# audio_chip.net
KiCad netlist of a schematic drawn in EasyEDA
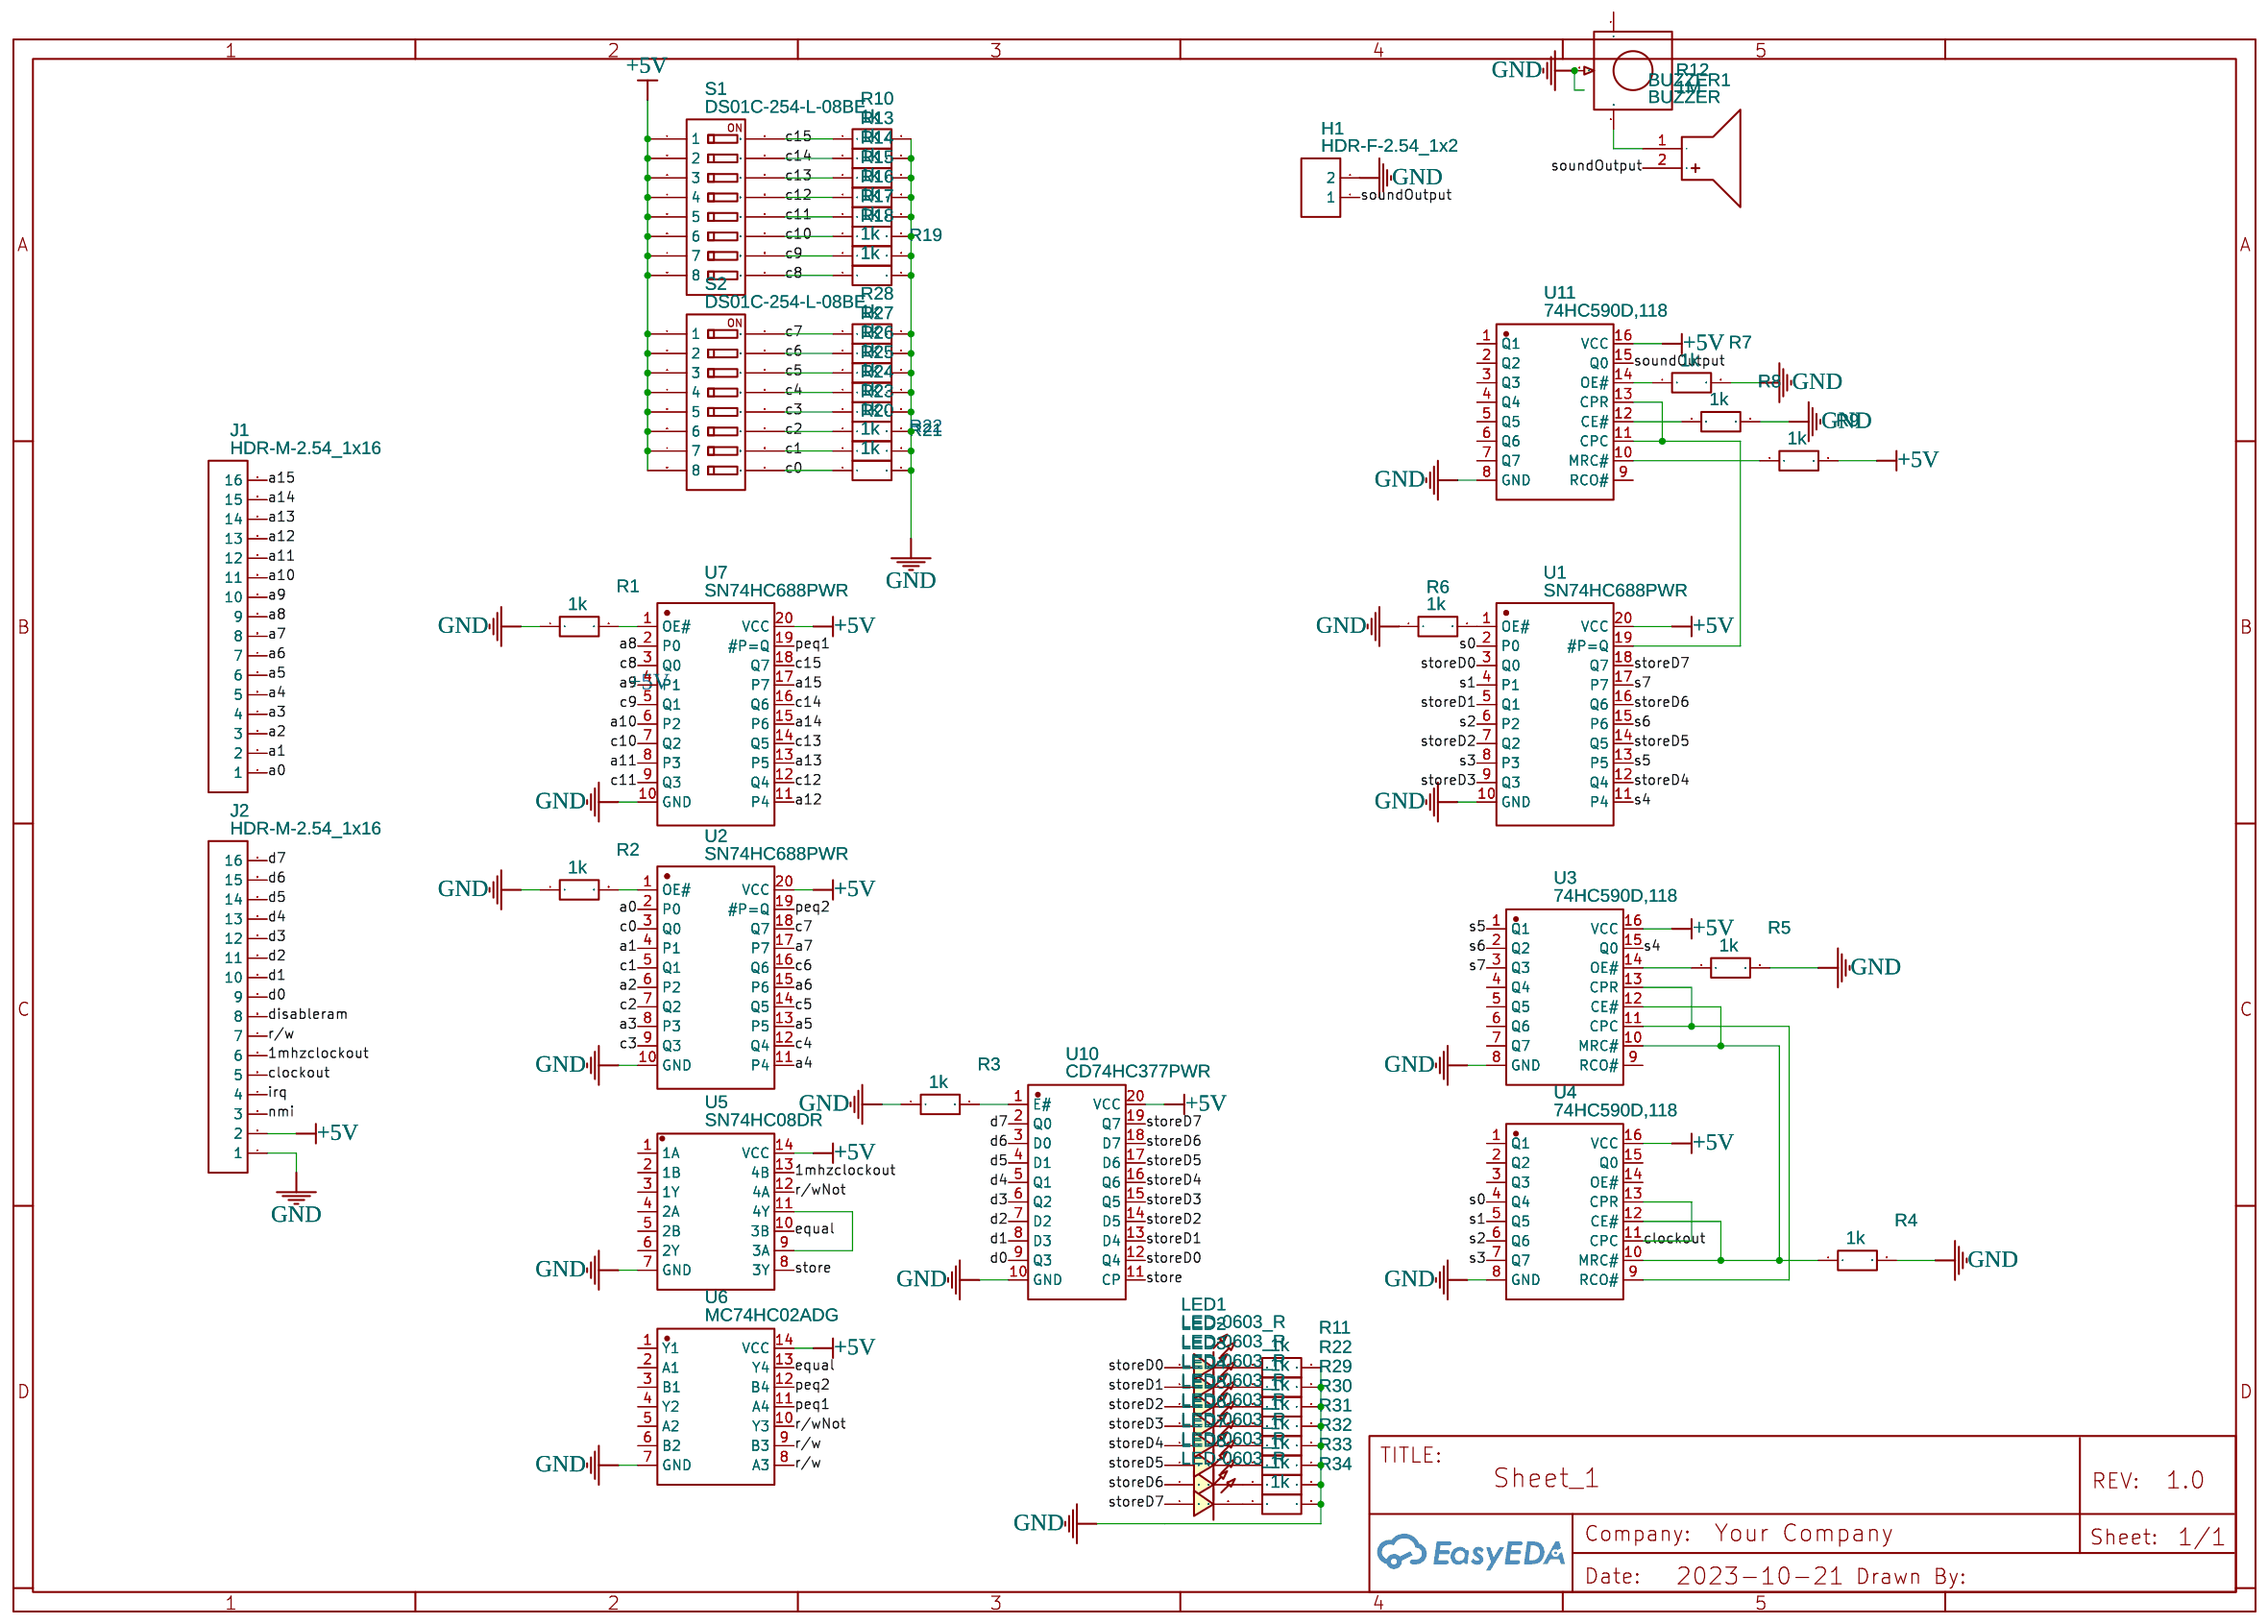
[diagram p0: schematic sheet]

(export (version "E")
  (design (tool "Eeschema 10.0.6"))
  (components
    (comp (ref "BUZZER1")
      (value "BUZZER")
      (fields (field (name "Manufacturer Part") "buzzer"))
      (libsource (lib "") (part "BUZZER"))
    )
    (comp (ref "H1") (value "HDR-F-2.54_1x2") (libsource (lib "") (part "HDR-F-2.54_1x2")))
    (comp (ref "J1") (value "HDR-M-2.54_1x16") (libsource (lib "") (part "HDR-M-2.54_1x16")))
    (comp (ref "J2") (value "HDR-M-2.54_1x16") (libsource (lib "") (part "HDR-M-2.54_1x16")))
    (comp (ref "LED1")
      (value "LED-0603_R")
      (fields
        (field (name "Manufacturer Part") "19-217/R6C-AL1M2VY/3T")
        (field (name "Manufacturer") "EVERLIGHT(台湾亿光)")
      )
      (libsource (lib "") (part "LED-0603_R"))
    )
    (comp (ref "LED2")
      (value "LED-0603_R")
      (fields
        (field (name "Manufacturer Part") "19-217/R6C-AL1M2VY/3T")
        (field (name "Manufacturer") "EVERLIGHT(台湾亿光)")
      )
      (libsource (lib "") (part "LED-0603_R"))
    )
    (comp (ref "LED3")
      (value "LED-0603_R")
      (fields
        (field (name "Manufacturer Part") "19-217/R6C-AL1M2VY/3T")
        (field (name "Manufacturer") "EVERLIGHT(台湾亿光)")
      )
      (libsource (lib "") (part "LED-0603_R"))
    )
    (comp (ref "LED4")
      (value "LED-0603_R")
      (fields
        (field (name "Manufacturer Part") "19-217/R6C-AL1M2VY/3T")
        (field (name "Manufacturer") "EVERLIGHT(台湾亿光)")
      )
      (libsource (lib "") (part "LED-0603_R"))
    )
    (comp (ref "LED5")
      (value "LED-0603_R")
      (fields
        (field (name "Manufacturer Part") "19-217/R6C-AL1M2VY/3T")
        (field (name "Manufacturer") "EVERLIGHT(台湾亿光)")
      )
      (libsource (lib "") (part "LED-0603_R"))
    )
    (comp (ref "LED6")
      (value "LED-0603_R")
      (fields
        (field (name "Manufacturer Part") "19-217/R6C-AL1M2VY/3T")
        (field (name "Manufacturer") "EVERLIGHT(台湾亿光)")
      )
      (libsource (lib "") (part "LED-0603_R"))
    )
    (comp (ref "LED7")
      (value "LED-0603_R")
      (fields
        (field (name "Manufacturer Part") "19-217/R6C-AL1M2VY/3T")
        (field (name "Manufacturer") "EVERLIGHT(台湾亿光)")
      )
      (libsource (lib "") (part "LED-0603_R"))
    )
    (comp (ref "LED8")
      (value "LED-0603_R")
      (fields
        (field (name "Manufacturer Part") "19-217/R6C-AL1M2VY/3T")
        (field (name "Manufacturer") "EVERLIGHT(台湾亿光)")
      )
      (libsource (lib "") (part "LED-0603_R"))
    )
    (comp (ref "R1") (value "1k") (libsource (lib "") (part "R_1206_EU")))
    (comp (ref "R2") (value "1k") (libsource (lib "") (part "R_1206_EU")))
    (comp (ref "R3") (value "1k") (libsource (lib "") (part "R_1206_EU")))
    (comp (ref "R4") (value "1k") (libsource (lib "") (part "R_1206_EU")))
    (comp (ref "R5") (value "1k") (libsource (lib "") (part "R_1206_EU")))
    (comp (ref "R6") (value "1k") (libsource (lib "") (part "R_1206_EU")))
    (comp (ref "R7") (value "1k") (libsource (lib "") (part "R_1206_EU")))
    (comp (ref "R8") (value "1k") (libsource (lib "") (part "R_1206_EU")))
    (comp (ref "R9") (value "1k") (libsource (lib "") (part "R_1206_EU")))
    (comp (ref "R10") (value "1k") (libsource (lib "") (part "R_1206_EU")))
    (comp (ref "R11") (value "1k") (libsource (lib "") (part "R_1206_EU")))
    (comp (ref "R12")
      (value "1M")
      (fields
        (field (name "Manufacturer Part") "3386T-1-LS1MEG(105)")
        (field (name "Manufacturer") "Jameco ValuePro")
      )
      (libsource (lib "") (part "3/8 Inch Square Cermet Potentiometer 1MEG Ohms 1/2 Watt 1 Turn Thru Hole"))
    )
    (comp (ref "R13") (value "1k") (libsource (lib "") (part "R_1206_EU")))
    (comp (ref "R14") (value "1k") (libsource (lib "") (part "R_1206_EU")))
    (comp (ref "R15") (value "1k") (libsource (lib "") (part "R_1206_EU")))
    (comp (ref "R16") (value "1k") (libsource (lib "") (part "R_1206_EU")))
    (comp (ref "R17") (value "1k") (libsource (lib "") (part "R_1206_EU")))
    (comp (ref "R18") (value "1k") (libsource (lib "") (part "R_1206_EU")))
    (comp (ref "R19") (value "1k") (libsource (lib "") (part "R_1206_EU")))
    (comp (ref "R20") (value "1k") (libsource (lib "") (part "R_1206_EU")))
    (comp (ref "R21") (value "1k") (libsource (lib "") (part "R_1206_EU")))
    (comp (ref "R22") (value "1k") (libsource (lib "") (part "R_1206_EU")))
    (comp (ref "R23") (value "1k") (libsource (lib "") (part "R_1206_EU")))
    (comp (ref "R24") (value "1k") (libsource (lib "") (part "R_1206_EU")))
    (comp (ref "R25") (value "1k") (libsource (lib "") (part "R_1206_EU")))
    (comp (ref "R26") (value "1k") (libsource (lib "") (part "R_1206_EU")))
    (comp (ref "R27") (value "1k") (libsource (lib "") (part "R_1206_EU")))
    (comp (ref "R28") (value "1k") (libsource (lib "") (part "R_1206_EU")))
    (comp (ref "R29") (value "1k") (libsource (lib "") (part "R_1206_EU")))
    (comp (ref "R30") (value "1k") (libsource (lib "") (part "R_1206_EU")))
    (comp (ref "R31") (value "1k") (libsource (lib "") (part "R_1206_EU")))
    (comp (ref "R32") (value "1k") (libsource (lib "") (part "R_1206_EU")))
    (comp (ref "R33") (value "1k") (libsource (lib "") (part "R_1206_EU")))
    (comp (ref "R34") (value "1k") (libsource (lib "") (part "R_1206_EU")))
    (comp (ref "S1")
      (value "DS01C-254-L-08BE")
      (fields
        (field (name "Manufacturer Part") "DS01C-254-L-07BE")
        (field (name "Manufacturer") "CUI Devices")
      )
      (libsource (lib "") (part "DS01C-254-L-08BE"))
    )
    (comp (ref "S2")
      (value "DS01C-254-L-08BE")
      (fields
        (field (name "Manufacturer Part") "DS01C-254-L-07BE")
        (field (name "Manufacturer") "CUI Devices")
      )
      (libsource (lib "") (part "DS01C-254-L-08BE"))
    )
    (comp (ref "U1")
      (value "SN74HC688PWR")
      (fields (field (name "Manufacturer") "TI(德州仪器)"))
      (libsource (lib "") (part "SN74HC688PWR"))
    )
    (comp (ref "U2")
      (value "SN74HC688PWR")
      (fields (field (name "Manufacturer") "TI(德州仪器)"))
      (libsource (lib "") (part "SN74HC688PWR"))
    )
    (comp (ref "U3")
      (value "74HC590D,118")
      (fields (field (name "Manufacturer") "Nexperia(安世)"))
      (libsource (lib "") (part "74HC590D,118"))
    )
    (comp (ref "U4")
      (value "74HC590D,118")
      (fields (field (name "Manufacturer") "Nexperia(安世)"))
      (libsource (lib "") (part "74HC590D,118"))
    )
    (comp (ref "U5")
      (value "SN74HC08DR")
      (fields (field (name "Manufacturer") "TI(德州仪器)"))
      (libsource (lib "") (part "SN74HC08DR"))
    )
    (comp (ref "U6")
      (value "MC74HC02ADG")
      (fields (field (name "Manufacturer") "onsemi(安森美)"))
      (libsource (lib "") (part "MC74HC02ADG"))
    )
    (comp (ref "U7")
      (value "SN74HC688PWR")
      (fields (field (name "Manufacturer") "TI(德州仪器)"))
      (libsource (lib "") (part "SN74HC688PWR"))
    )
    (comp (ref "U10")
      (value "CD74HC377PWR")
      (fields (field (name "Manufacturer") "TI(德州仪器)"))
      (libsource (lib "") (part "CD74HC377PWR"))
    )
    (comp (ref "U11")
      (value "74HC590D,118")
      (fields (field (name "Manufacturer") "Nexperia(安世)"))
      (libsource (lib "") (part "74HC590D,118"))
    )
  )
  (nets
    (net (code "1") (name "+5V") (class "Default")
      (node (ref "J2") (pin "2") (pinfunction "2_2") (pintype "unspecified"))
      (node (ref "R9") (pin "2") (pinfunction "2_2") (pintype "unspecified"))
      (node (ref "S1") (pin "1") (pinfunction "1_1") (pintype "unspecified"))
      (node (ref "S1") (pin "2") (pinfunction "2_2") (pintype "unspecified"))
      (node (ref "S1") (pin "3") (pinfunction "3_3") (pintype "unspecified"))
      (node (ref "S1") (pin "4") (pinfunction "4_4") (pintype "unspecified"))
      (node (ref "S1") (pin "5") (pinfunction "5_5") (pintype "unspecified"))
      (node (ref "S1") (pin "6") (pinfunction "6_6") (pintype "unspecified"))
      (node (ref "S1") (pin "7") (pinfunction "7_7") (pintype "unspecified"))
      (node (ref "S1") (pin "8") (pinfunction "8_8") (pintype "unspecified"))
      (node (ref "S2") (pin "1") (pinfunction "1_1") (pintype "unspecified"))
      (node (ref "S2") (pin "2") (pinfunction "2_2") (pintype "unspecified"))
      (node (ref "S2") (pin "3") (pinfunction "3_3") (pintype "unspecified"))
      (node (ref "S2") (pin "4") (pinfunction "4_4") (pintype "unspecified"))
      (node (ref "S2") (pin "5") (pinfunction "5_5") (pintype "unspecified"))
      (node (ref "S2") (pin "6") (pinfunction "6_6") (pintype "unspecified"))
      (node (ref "S2") (pin "7") (pinfunction "7_7") (pintype "unspecified"))
      (node (ref "S2") (pin "8") (pinfunction "8_8") (pintype "unspecified"))
      (node (ref "U1") (pin "20") (pinfunction "VCC_20") (pintype "unspecified"))
      (node (ref "U10") (pin "20") (pinfunction "VCC_20") (pintype "unspecified"))
      (node (ref "U11") (pin "16") (pinfunction "VCC_16") (pintype "unspecified"))
      (node (ref "U2") (pin "20") (pinfunction "VCC_20") (pintype "unspecified"))
      (node (ref "U3") (pin "16") (pinfunction "VCC_16") (pintype "unspecified"))
      (node (ref "U4") (pin "16") (pinfunction "VCC_16") (pintype "unspecified"))
      (node (ref "U5") (pin "14") (pinfunction "VCC_14") (pintype "unspecified"))
      (node (ref "U6") (pin "14") (pinfunction "VCC_14") (pintype "unspecified"))
      (node (ref "U7") (pin "20") (pinfunction "VCC_20") (pintype "unspecified"))
    )
    (net (code "2") (name "/1mhzclockout") (class "Default")
      (node (ref "J2") (pin "6") (pinfunction "6_6") (pintype "unspecified"))
      (node (ref "U5") (pin "13") (pinfunction "4B_13") (pintype "unspecified"))
    )
    (net (code "3") (name "/a0") (class "Default")
      (node (ref "J1") (pin "1") (pinfunction "1_1") (pintype "unspecified"))
      (node (ref "U2") (pin "2") (pinfunction "P0_2") (pintype "unspecified"))
    )
    (net (code "4") (name "/a1") (class "Default")
      (node (ref "J1") (pin "2") (pinfunction "2_2") (pintype "unspecified"))
      (node (ref "U2") (pin "4") (pinfunction "P1_4") (pintype "unspecified"))
    )
    (net (code "5") (name "/a2") (class "Default")
      (node (ref "J1") (pin "3") (pinfunction "3_3") (pintype "unspecified"))
      (node (ref "U2") (pin "6") (pinfunction "P2_6") (pintype "unspecified"))
    )
    (net (code "6") (name "/a3") (class "Default")
      (node (ref "J1") (pin "4") (pinfunction "4_4") (pintype "unspecified"))
      (node (ref "U2") (pin "8") (pinfunction "P3_8") (pintype "unspecified"))
    )
    (net (code "7") (name "/a4") (class "Default")
      (node (ref "J1") (pin "5") (pinfunction "5_5") (pintype "unspecified"))
      (node (ref "U2") (pin "11") (pinfunction "P4_11") (pintype "unspecified"))
    )
    (net (code "8") (name "/a5") (class "Default")
      (node (ref "J1") (pin "6") (pinfunction "6_6") (pintype "unspecified"))
      (node (ref "U2") (pin "13") (pinfunction "P5_13") (pintype "unspecified"))
    )
    (net (code "9") (name "/a6") (class "Default")
      (node (ref "J1") (pin "7") (pinfunction "7_7") (pintype "unspecified"))
      (node (ref "U2") (pin "15") (pinfunction "P6_15") (pintype "unspecified"))
    )
    (net (code "10") (name "/a7") (class "Default")
      (node (ref "J1") (pin "8") (pinfunction "8_8") (pintype "unspecified"))
      (node (ref "U2") (pin "17") (pinfunction "P7_17") (pintype "unspecified"))
    )
    (net (code "11") (name "/a8") (class "Default")
      (node (ref "J1") (pin "9") (pinfunction "9_9") (pintype "unspecified"))
      (node (ref "U7") (pin "2") (pinfunction "P0_2") (pintype "unspecified"))
    )
    (net (code "12") (name "/a9") (class "Default")
      (node (ref "J1") (pin "10") (pinfunction "10_10") (pintype "unspecified"))
      (node (ref "U7") (pin "4") (pinfunction "P1_4") (pintype "unspecified"))
    )
    (net (code "13") (name "/a10") (class "Default")
      (node (ref "J1") (pin "11") (pinfunction "11_11") (pintype "unspecified"))
      (node (ref "U7") (pin "6") (pinfunction "P2_6") (pintype "unspecified"))
    )
    (net (code "14") (name "/a11") (class "Default")
      (node (ref "J1") (pin "12") (pinfunction "12_12") (pintype "unspecified"))
      (node (ref "U7") (pin "8") (pinfunction "P3_8") (pintype "unspecified"))
    )
    (net (code "15") (name "/a12") (class "Default")
      (node (ref "J1") (pin "13") (pinfunction "13_13") (pintype "unspecified"))
      (node (ref "U7") (pin "11") (pinfunction "P4_11") (pintype "unspecified"))
    )
    (net (code "16") (name "/a13") (class "Default")
      (node (ref "J1") (pin "14") (pinfunction "14_14") (pintype "unspecified"))
      (node (ref "U7") (pin "13") (pinfunction "P5_13") (pintype "unspecified"))
    )
    (net (code "17") (name "/a14") (class "Default")
      (node (ref "J1") (pin "15") (pinfunction "15_15") (pintype "unspecified"))
      (node (ref "U7") (pin "15") (pinfunction "P6_15") (pintype "unspecified"))
    )
    (net (code "18") (name "/a15") (class "Default")
      (node (ref "J1") (pin "16") (pinfunction "16_16") (pintype "unspecified"))
      (node (ref "U7") (pin "17") (pinfunction "P7_17") (pintype "unspecified"))
    )
    (net (code "19") (name "/c0") (class "Default")
      (node (ref "R21") (pin "1") (pinfunction "1_1") (pintype "unspecified"))
      (node (ref "S2") (pin "9") (pinfunction "9_9") (pintype "unspecified"))
      (node (ref "U2") (pin "3") (pinfunction "Q0_3") (pintype "unspecified"))
    )
    (net (code "20") (name "/c1") (class "Default")
      (node (ref "R20") (pin "1") (pinfunction "1_1") (pintype "unspecified"))
      (node (ref "S2") (pin "10") (pinfunction "10_10") (pintype "unspecified"))
      (node (ref "U2") (pin "5") (pinfunction "Q1_5") (pintype "unspecified"))
    )
    (net (code "21") (name "/c2") (class "Default")
      (node (ref "R23") (pin "1") (pinfunction "1_1") (pintype "unspecified"))
      (node (ref "S2") (pin "11") (pinfunction "11_11") (pintype "unspecified"))
      (node (ref "U2") (pin "7") (pinfunction "Q2_7") (pintype "unspecified"))
    )
    (net (code "22") (name "/c3") (class "Default")
      (node (ref "R24") (pin "1") (pinfunction "1_1") (pintype "unspecified"))
      (node (ref "S2") (pin "12") (pinfunction "12_12") (pintype "unspecified"))
      (node (ref "U2") (pin "9") (pinfunction "Q3_9") (pintype "unspecified"))
    )
    (net (code "23") (name "/c4") (class "Default")
      (node (ref "R25") (pin "1") (pinfunction "1_1") (pintype "unspecified"))
      (node (ref "S2") (pin "13") (pinfunction "13_13") (pintype "unspecified"))
      (node (ref "U2") (pin "12") (pinfunction "Q4_12") (pintype "unspecified"))
    )
    (net (code "24") (name "/c5") (class "Default")
      (node (ref "R26") (pin "1") (pinfunction "1_1") (pintype "unspecified"))
      (node (ref "S2") (pin "14") (pinfunction "14_14") (pintype "unspecified"))
      (node (ref "U2") (pin "14") (pinfunction "Q5_14") (pintype "unspecified"))
    )
    (net (code "25") (name "/c6") (class "Default")
      (node (ref "R27") (pin "1") (pinfunction "1_1") (pintype "unspecified"))
      (node (ref "S2") (pin "15") (pinfunction "15_15") (pintype "unspecified"))
      (node (ref "U2") (pin "16") (pinfunction "Q6_16") (pintype "unspecified"))
    )
    (net (code "26") (name "/c7") (class "Default")
      (node (ref "R28") (pin "1") (pinfunction "1_1") (pintype "unspecified"))
      (node (ref "S2") (pin "16") (pinfunction "16_16") (pintype "unspecified"))
      (node (ref "U2") (pin "18") (pinfunction "Q7_18") (pintype "unspecified"))
    )
    (net (code "27") (name "/c8") (class "Default")
      (node (ref "R19") (pin "1") (pinfunction "1_1") (pintype "unspecified"))
      (node (ref "S1") (pin "9") (pinfunction "9_9") (pintype "unspecified"))
      (node (ref "U7") (pin "3") (pinfunction "Q0_3") (pintype "unspecified"))
    )
    (net (code "28") (name "/c9") (class "Default")
      (node (ref "R18") (pin "1") (pinfunction "1_1") (pintype "unspecified"))
      (node (ref "S1") (pin "10") (pinfunction "10_10") (pintype "unspecified"))
      (node (ref "U7") (pin "5") (pinfunction "Q1_5") (pintype "unspecified"))
    )
    (net (code "29") (name "/c10") (class "Default")
      (node (ref "R17") (pin "1") (pinfunction "1_1") (pintype "unspecified"))
      (node (ref "S1") (pin "11") (pinfunction "11_11") (pintype "unspecified"))
      (node (ref "U7") (pin "7") (pinfunction "Q2_7") (pintype "unspecified"))
    )
    (net (code "30") (name "/c11") (class "Default")
      (node (ref "R16") (pin "1") (pinfunction "1_1") (pintype "unspecified"))
      (node (ref "S1") (pin "12") (pinfunction "12_12") (pintype "unspecified"))
      (node (ref "U7") (pin "9") (pinfunction "Q3_9") (pintype "unspecified"))
    )
    (net (code "31") (name "/c12") (class "Default")
      (node (ref "R15") (pin "1") (pinfunction "1_1") (pintype "unspecified"))
      (node (ref "S1") (pin "13") (pinfunction "13_13") (pintype "unspecified"))
      (node (ref "U7") (pin "12") (pinfunction "Q4_12") (pintype "unspecified"))
    )
    (net (code "32") (name "/c13") (class "Default")
      (node (ref "R14") (pin "1") (pinfunction "1_1") (pintype "unspecified"))
      (node (ref "S1") (pin "14") (pinfunction "14_14") (pintype "unspecified"))
      (node (ref "U7") (pin "14") (pinfunction "Q5_14") (pintype "unspecified"))
    )
    (net (code "33") (name "/c14") (class "Default")
      (node (ref "R13") (pin "1") (pinfunction "1_1") (pintype "unspecified"))
      (node (ref "S1") (pin "15") (pinfunction "15_15") (pintype "unspecified"))
      (node (ref "U7") (pin "16") (pinfunction "Q6_16") (pintype "unspecified"))
    )
    (net (code "34") (name "/c15") (class "Default")
      (node (ref "R10") (pin "1") (pinfunction "1_1") (pintype "unspecified"))
      (node (ref "S1") (pin "16") (pinfunction "16_16") (pintype "unspecified"))
      (node (ref "U7") (pin "18") (pinfunction "Q7_18") (pintype "unspecified"))
    )
    (net (code "35") (name "/clockout") (class "Default")
      (node (ref "J2") (pin "5") (pinfunction "5_5") (pintype "unspecified"))
      (node (ref "U4") (pin "11") (pinfunction "CPC_11") (pintype "unspecified"))
      (node (ref "U4") (pin "13") (pinfunction "CPR_13") (pintype "unspecified"))
    )
    (net (code "36") (name "/d0") (class "Default")
      (node (ref "J2") (pin "9") (pinfunction "9_9") (pintype "unspecified"))
      (node (ref "U10") (pin "9") (pinfunction "Q3_9") (pintype "unspecified"))
    )
    (net (code "37") (name "/d1") (class "Default")
      (node (ref "J2") (pin "10") (pinfunction "10_10") (pintype "unspecified"))
      (node (ref "U10") (pin "8") (pinfunction "D3_8") (pintype "unspecified"))
    )
    (net (code "38") (name "/d2") (class "Default")
      (node (ref "J2") (pin "11") (pinfunction "11_11") (pintype "unspecified"))
      (node (ref "U10") (pin "7") (pinfunction "D2_7") (pintype "unspecified"))
    )
    (net (code "39") (name "/d3") (class "Default")
      (node (ref "J2") (pin "12") (pinfunction "12_12") (pintype "unspecified"))
      (node (ref "U10") (pin "6") (pinfunction "Q2_6") (pintype "unspecified"))
    )
    (net (code "40") (name "/d4") (class "Default")
      (node (ref "J2") (pin "13") (pinfunction "13_13") (pintype "unspecified"))
      (node (ref "U10") (pin "5") (pinfunction "Q1_5") (pintype "unspecified"))
    )
    (net (code "41") (name "/d5") (class "Default")
      (node (ref "J2") (pin "14") (pinfunction "14_14") (pintype "unspecified"))
      (node (ref "U10") (pin "4") (pinfunction "D1_4") (pintype "unspecified"))
    )
    (net (code "42") (name "/d6") (class "Default")
      (node (ref "J2") (pin "15") (pinfunction "15_15") (pintype "unspecified"))
      (node (ref "U10") (pin "3") (pinfunction "D0_3") (pintype "unspecified"))
    )
    (net (code "43") (name "/d7") (class "Default")
      (node (ref "J2") (pin "16") (pinfunction "16_16") (pintype "unspecified"))
      (node (ref "U10") (pin "2") (pinfunction "Q0_2") (pintype "unspecified"))
    )
    (net (code "44") (name "/disableram") (class "Default")
      (node (ref "J2") (pin "8") (pinfunction "8_8") (pintype "unspecified"))
    )
    (net (code "45") (name "/equal") (class "Default")
      (node (ref "U5") (pin "10") (pinfunction "3B_10") (pintype "unspecified"))
      (node (ref "U6") (pin "13") (pinfunction "Y4_13") (pintype "unspecified"))
    )
    (net (code "46") (name "/irq") (class "Default")
      (node (ref "J2") (pin "4") (pinfunction "4_4") (pintype "unspecified"))
    )
    (net (code "47") (name "/nmi") (class "Default")
      (node (ref "J2") (pin "3") (pinfunction "3_3") (pintype "unspecified"))
    )
    (net (code "48") (name "/peq1") (class "Default")
      (node (ref "U6") (pin "11") (pinfunction "A4_11") (pintype "unspecified"))
      (node (ref "U7") (pin "19") (pinfunction "#P=Q_19") (pintype "unspecified"))
    )
    (net (code "49") (name "/peq2") (class "Default")
      (node (ref "U2") (pin "19") (pinfunction "#P=Q_19") (pintype "unspecified"))
      (node (ref "U6") (pin "12") (pinfunction "B4_12") (pintype "unspecified"))
    )
    (net (code "50") (name "/r{slash}w") (class "Default")
      (node (ref "J2") (pin "7") (pinfunction "7_7") (pintype "unspecified"))
      (node (ref "U6") (pin "8") (pinfunction "A3_8") (pintype "unspecified"))
      (node (ref "U6") (pin "9") (pinfunction "B3_9") (pintype "unspecified"))
    )
    (net (code "51") (name "/r{slash}wNot") (class "Default")
      (node (ref "U5") (pin "12") (pinfunction "4A_12") (pintype "unspecified"))
      (node (ref "U6") (pin "10") (pinfunction "Y3_10") (pintype "unspecified"))
    )
    (net (code "52") (name "/s0") (class "Default")
      (node (ref "U1") (pin "2") (pinfunction "P0_2") (pintype "unspecified"))
      (node (ref "U4") (pin "4") (pinfunction "Q4_4") (pintype "unspecified"))
    )
    (net (code "53") (name "/s1") (class "Default")
      (node (ref "U1") (pin "4") (pinfunction "P1_4") (pintype "unspecified"))
      (node (ref "U4") (pin "5") (pinfunction "Q5_5") (pintype "unspecified"))
    )
    (net (code "54") (name "/s2") (class "Default")
      (node (ref "U1") (pin "6") (pinfunction "P2_6") (pintype "unspecified"))
      (node (ref "U4") (pin "6") (pinfunction "Q6_6") (pintype "unspecified"))
    )
    (net (code "55") (name "/s3") (class "Default")
      (node (ref "U1") (pin "8") (pinfunction "P3_8") (pintype "unspecified"))
      (node (ref "U4") (pin "7") (pinfunction "Q7_7") (pintype "unspecified"))
    )
    (net (code "56") (name "/s4") (class "Default")
      (node (ref "U1") (pin "11") (pinfunction "P4_11") (pintype "unspecified"))
      (node (ref "U3") (pin "15") (pinfunction "Q0_15") (pintype "unspecified"))
    )
    (net (code "57") (name "/s5") (class "Default")
      (node (ref "U1") (pin "13") (pinfunction "P5_13") (pintype "unspecified"))
      (node (ref "U3") (pin "1") (pinfunction "Q1_1") (pintype "unspecified"))
    )
    (net (code "58") (name "/s6") (class "Default")
      (node (ref "U1") (pin "15") (pinfunction "P6_15") (pintype "unspecified"))
      (node (ref "U3") (pin "2") (pinfunction "Q2_2") (pintype "unspecified"))
    )
    (net (code "59") (name "/s7") (class "Default")
      (node (ref "U1") (pin "17") (pinfunction "P7_17") (pintype "unspecified"))
      (node (ref "U3") (pin "3") (pinfunction "Q3_3") (pintype "unspecified"))
    )
    (net (code "60") (name "/soundOutput") (class "Default")
      (node (ref "BUZZER1") (pin "2") (pinfunction "+_2") (pintype "unspecified"))
      (node (ref "H1") (pin "1") (pinfunction "1_1") (pintype "input"))
      (node (ref "U11") (pin "15") (pinfunction "Q0_15") (pintype "unspecified"))
    )
    (net (code "61") (name "/store") (class "Default")
      (node (ref "U10") (pin "11") (pinfunction "CP_11") (pintype "unspecified"))
      (node (ref "U5") (pin "8") (pinfunction "3Y_8") (pintype "unspecified"))
    )
    (net (code "62") (name "/storeD0") (class "Default")
      (node (ref "LED1") (pin "1") (pinfunction "1_1") (pintype "unspecified"))
      (node (ref "U1") (pin "3") (pinfunction "Q0_3") (pintype "unspecified"))
      (node (ref "U10") (pin "12") (pinfunction "Q4_12") (pintype "unspecified"))
    )
    (net (code "63") (name "/storeD1") (class "Default")
      (node (ref "LED2") (pin "1") (pinfunction "1_1") (pintype "unspecified"))
      (node (ref "U1") (pin "5") (pinfunction "Q1_5") (pintype "unspecified"))
      (node (ref "U10") (pin "13") (pinfunction "D4_13") (pintype "unspecified"))
    )
    (net (code "64") (name "/storeD2") (class "Default")
      (node (ref "LED3") (pin "1") (pinfunction "1_1") (pintype "unspecified"))
      (node (ref "U1") (pin "7") (pinfunction "Q2_7") (pintype "unspecified"))
      (node (ref "U10") (pin "14") (pinfunction "D5_14") (pintype "unspecified"))
    )
    (net (code "65") (name "/storeD3") (class "Default")
      (node (ref "LED4") (pin "1") (pinfunction "1_1") (pintype "unspecified"))
      (node (ref "U1") (pin "9") (pinfunction "Q3_9") (pintype "unspecified"))
      (node (ref "U10") (pin "15") (pinfunction "Q5_15") (pintype "unspecified"))
    )
    (net (code "66") (name "/storeD4") (class "Default")
      (node (ref "LED5") (pin "1") (pinfunction "1_1") (pintype "unspecified"))
      (node (ref "U1") (pin "12") (pinfunction "Q4_12") (pintype "unspecified"))
      (node (ref "U10") (pin "16") (pinfunction "Q6_16") (pintype "unspecified"))
    )
    (net (code "67") (name "/storeD5") (class "Default")
      (node (ref "LED6") (pin "1") (pinfunction "1_1") (pintype "unspecified"))
      (node (ref "U1") (pin "14") (pinfunction "Q5_14") (pintype "unspecified"))
      (node (ref "U10") (pin "17") (pinfunction "D6_17") (pintype "unspecified"))
    )
    (net (code "68") (name "/storeD6") (class "Default")
      (node (ref "LED7") (pin "1") (pinfunction "1_1") (pintype "unspecified"))
      (node (ref "U1") (pin "16") (pinfunction "Q6_16") (pintype "unspecified"))
      (node (ref "U10") (pin "18") (pinfunction "D7_18") (pintype "unspecified"))
    )
    (net (code "69") (name "/storeD7") (class "Default")
      (node (ref "LED8") (pin "1") (pinfunction "1_1") (pintype "unspecified"))
      (node (ref "U1") (pin "18") (pinfunction "Q7_18") (pintype "unspecified"))
      (node (ref "U10") (pin "19") (pinfunction "Q7_19") (pintype "unspecified"))
    )
    (net (code "70") (name "GND") (class "Default")
      (node (ref "H1") (pin "2") (pinfunction "2_2") (pintype "input"))
      (node (ref "J2") (pin "1") (pinfunction "1_1") (pintype "unspecified"))
      (node (ref "R1") (pin "1") (pinfunction "1_1") (pintype "unspecified"))
      (node (ref "R10") (pin "2") (pinfunction "2_2") (pintype "unspecified"))
      (node (ref "R11") (pin "2") (pinfunction "2_2") (pintype "unspecified"))
      (node (ref "R12") (pin "2") (pinfunction "2_2") (pintype "unspecified"))
      (node (ref "R13") (pin "2") (pinfunction "2_2") (pintype "unspecified"))
      (node (ref "R14") (pin "2") (pinfunction "2_2") (pintype "unspecified"))
      (node (ref "R15") (pin "2") (pinfunction "2_2") (pintype "unspecified"))
      (node (ref "R16") (pin "2") (pinfunction "2_2") (pintype "unspecified"))
      (node (ref "R17") (pin "2") (pinfunction "2_2") (pintype "unspecified"))
      (node (ref "R18") (pin "2") (pinfunction "2_2") (pintype "unspecified"))
      (node (ref "R19") (pin "2") (pinfunction "2_2") (pintype "unspecified"))
      (node (ref "R2") (pin "1") (pinfunction "1_1") (pintype "unspecified"))
      (node (ref "R20") (pin "2") (pinfunction "2_2") (pintype "unspecified"))
      (node (ref "R21") (pin "2") (pinfunction "2_2") (pintype "unspecified"))
      (node (ref "R22") (pin "2") (pinfunction "2_2") (pintype "unspecified"))
      (node (ref "R23") (pin "2") (pinfunction "2_2") (pintype "unspecified"))
      (node (ref "R24") (pin "2") (pinfunction "2_2") (pintype "unspecified"))
      (node (ref "R25") (pin "2") (pinfunction "2_2") (pintype "unspecified"))
      (node (ref "R26") (pin "2") (pinfunction "2_2") (pintype "unspecified"))
      (node (ref "R27") (pin "2") (pinfunction "2_2") (pintype "unspecified"))
      (node (ref "R28") (pin "2") (pinfunction "2_2") (pintype "unspecified"))
      (node (ref "R29") (pin "2") (pinfunction "2_2") (pintype "unspecified"))
      (node (ref "R3") (pin "1") (pinfunction "1_1") (pintype "unspecified"))
      (node (ref "R30") (pin "2") (pinfunction "2_2") (pintype "unspecified"))
      (node (ref "R31") (pin "2") (pinfunction "2_2") (pintype "unspecified"))
      (node (ref "R32") (pin "2") (pinfunction "2_2") (pintype "unspecified"))
      (node (ref "R33") (pin "2") (pinfunction "2_2") (pintype "unspecified"))
      (node (ref "R34") (pin "2") (pinfunction "2_2") (pintype "unspecified"))
      (node (ref "R4") (pin "2") (pinfunction "2_2") (pintype "unspecified"))
      (node (ref "R5") (pin "2") (pinfunction "2_2") (pintype "unspecified"))
      (node (ref "R6") (pin "1") (pinfunction "1_1") (pintype "unspecified"))
      (node (ref "R7") (pin "2") (pinfunction "2_2") (pintype "unspecified"))
      (node (ref "R8") (pin "2") (pinfunction "2_2") (pintype "unspecified"))
      (node (ref "U1") (pin "10") (pinfunction "GND_10") (pintype "unspecified"))
      (node (ref "U10") (pin "10") (pinfunction "GND_10") (pintype "unspecified"))
      (node (ref "U11") (pin "8") (pinfunction "GND_8") (pintype "unspecified"))
      (node (ref "U2") (pin "10") (pinfunction "GND_10") (pintype "unspecified"))
      (node (ref "U3") (pin "8") (pinfunction "GND_8") (pintype "unspecified"))
      (node (ref "U4") (pin "8") (pinfunction "GND_8") (pintype "unspecified"))
      (node (ref "U5") (pin "7") (pinfunction "GND_7") (pintype "unspecified"))
      (node (ref "U6") (pin "7") (pinfunction "GND_7") (pintype "unspecified"))
      (node (ref "U7") (pin "10") (pinfunction "GND_10") (pintype "unspecified"))
    )
    (net (code "71") (name "Net-(BUZZER1--)") (class "Default")
      (node (ref "BUZZER1") (pin "1") (pinfunction "-_1") (pintype "unspecified"))
      (node (ref "R12") (pin "3") (pinfunction "3_3") (pintype "unspecified"))
    )
    (net (code "72") (name "Net-(LED1-Pad2)") (class "Default")
      (node (ref "LED1") (pin "2") (pinfunction "2_2") (pintype "unspecified"))
      (node (ref "R11") (pin "1") (pinfunction "1_1") (pintype "unspecified"))
    )
    (net (code "73") (name "Net-(LED2-Pad2)") (class "Default")
      (node (ref "LED2") (pin "2") (pinfunction "2_2") (pintype "unspecified"))
      (node (ref "R22") (pin "1") (pinfunction "1_1") (pintype "unspecified"))
    )
    (net (code "74") (name "Net-(LED3-Pad2)") (class "Default")
      (node (ref "LED3") (pin "2") (pinfunction "2_2") (pintype "unspecified"))
      (node (ref "R29") (pin "1") (pinfunction "1_1") (pintype "unspecified"))
    )
    (net (code "75") (name "Net-(LED4-Pad2)") (class "Default")
      (node (ref "LED4") (pin "2") (pinfunction "2_2") (pintype "unspecified"))
      (node (ref "R30") (pin "1") (pinfunction "1_1") (pintype "unspecified"))
    )
    (net (code "76") (name "Net-(LED5-Pad2)") (class "Default")
      (node (ref "LED5") (pin "2") (pinfunction "2_2") (pintype "unspecified"))
      (node (ref "R31") (pin "1") (pinfunction "1_1") (pintype "unspecified"))
    )
    (net (code "77") (name "Net-(LED6-Pad2)") (class "Default")
      (node (ref "LED6") (pin "2") (pinfunction "2_2") (pintype "unspecified"))
      (node (ref "R32") (pin "1") (pinfunction "1_1") (pintype "unspecified"))
    )
    (net (code "78") (name "Net-(LED7-Pad2)") (class "Default")
      (node (ref "LED7") (pin "2") (pinfunction "2_2") (pintype "unspecified"))
      (node (ref "R33") (pin "1") (pinfunction "1_1") (pintype "unspecified"))
    )
    (net (code "79") (name "Net-(LED8-Pad2)") (class "Default")
      (node (ref "LED8") (pin "2") (pinfunction "2_2") (pintype "unspecified"))
      (node (ref "R34") (pin "1") (pinfunction "1_1") (pintype "unspecified"))
    )
    (net (code "80") (name "Net-(U1-#P=Q)") (class "Default")
      (node (ref "U1") (pin "19") (pinfunction "#P=Q_19") (pintype "unspecified"))
      (node (ref "U11") (pin "11") (pinfunction "CPC_11") (pintype "unspecified"))
      (node (ref "U11") (pin "13") (pinfunction "CPR_13") (pintype "unspecified"))
    )
    (net (code "81") (name "Net-(U1-OE#)") (class "Default")
      (node (ref "R6") (pin "2") (pinfunction "2_2") (pintype "unspecified"))
      (node (ref "U1") (pin "1") (pinfunction "OE#_1") (pintype "unspecified"))
    )
    (net (code "82") (name "Net-(U2-OE#)") (class "Default")
      (node (ref "R2") (pin "2") (pinfunction "2_2") (pintype "unspecified"))
      (node (ref "U2") (pin "1") (pinfunction "OE#_1") (pintype "unspecified"))
    )
    (net (code "83") (name "Net-(U3-CE#)") (class "Default")
      (node (ref "R4") (pin "1") (pinfunction "1_1") (pintype "unspecified"))
      (node (ref "U3") (pin "10") (pinfunction "MRC#_10") (pintype "unspecified"))
      (node (ref "U3") (pin "12") (pinfunction "CE#_12") (pintype "unspecified"))
      (node (ref "U4") (pin "10") (pinfunction "MRC#_10") (pintype "unspecified"))
      (node (ref "U4") (pin "12") (pinfunction "CE#_12") (pintype "unspecified"))
    )
    (net (code "84") (name "Net-(U3-CPC)") (class "Default")
      (node (ref "U3") (pin "11") (pinfunction "CPC_11") (pintype "unspecified"))
      (node (ref "U3") (pin "13") (pinfunction "CPR_13") (pintype "unspecified"))
      (node (ref "U4") (pin "9") (pinfunction "RCO#_9") (pintype "unspecified"))
    )
    (net (code "85") (name "Net-(U3-OE#)") (class "Default")
      (node (ref "R5") (pin "1") (pinfunction "1_1") (pintype "unspecified"))
      (node (ref "U3") (pin "14") (pinfunction "OE#_14") (pintype "unspecified"))
    )
    (net (code "86") (name "Net-(U5-3A)") (class "Default")
      (node (ref "U5") (pin "11") (pinfunction "4Y_11") (pintype "unspecified"))
      (node (ref "U5") (pin "9") (pinfunction "3A_9") (pintype "unspecified"))
    )
    (net (code "87") (name "Net-(U7-OE#)") (class "Default")
      (node (ref "R1") (pin "2") (pinfunction "2_2") (pintype "unspecified"))
      (node (ref "U7") (pin "1") (pinfunction "OE#_1") (pintype "unspecified"))
    )
    (net (code "88") (name "Net-(U10-E#)") (class "Default")
      (node (ref "R3") (pin "2") (pinfunction "2_2") (pintype "unspecified"))
      (node (ref "U10") (pin "1") (pinfunction "E#_1") (pintype "unspecified"))
    )
    (net (code "89") (name "Net-(U11-CE#)") (class "Default")
      (node (ref "R8") (pin "1") (pinfunction "1_1") (pintype "unspecified"))
      (node (ref "U11") (pin "12") (pinfunction "CE#_12") (pintype "unspecified"))
    )
    (net (code "90") (name "Net-(U11-MRC#)") (class "Default")
      (node (ref "R9") (pin "1") (pinfunction "1_1") (pintype "unspecified"))
      (node (ref "U11") (pin "10") (pinfunction "MRC#_10") (pintype "unspecified"))
    )
    (net (code "91") (name "Net-(U11-OE#)") (class "Default")
      (node (ref "R7") (pin "1") (pinfunction "1_1") (pintype "unspecified"))
      (node (ref "U11") (pin "14") (pinfunction "OE#_14") (pintype "unspecified"))
    )
    (net (code "92") (name "unconnected-(R12-Pad1)") (class "Default")
      (node (ref "R12") (pin "1") (pinfunction "1_1") (pintype "unspecified"))
    )
    (net (code "93") (name "unconnected-(U3-Q4-Pad4)") (class "Default")
      (node (ref "U3") (pin "4") (pinfunction "Q4_4") (pintype "unspecified"))
    )
    (net (code "94") (name "unconnected-(U3-Q5-Pad5)") (class "Default")
      (node (ref "U3") (pin "5") (pinfunction "Q5_5") (pintype "unspecified"))
    )
    (net (code "95") (name "unconnected-(U3-Q6-Pad6)") (class "Default")
      (node (ref "U3") (pin "6") (pinfunction "Q6_6") (pintype "unspecified"))
    )
    (net (code "96") (name "unconnected-(U3-Q7-Pad7)") (class "Default")
      (node (ref "U3") (pin "7") (pinfunction "Q7_7") (pintype "unspecified"))
    )
    (net (code "97") (name "unconnected-(U3-RCO#-Pad9)") (class "Default")
      (node (ref "U3") (pin "9") (pinfunction "RCO#_9") (pintype "unspecified"))
    )
    (net (code "98") (name "unconnected-(U4-OE#-Pad14)") (class "Default")
      (node (ref "U4") (pin "14") (pinfunction "OE#_14") (pintype "unspecified"))
    )
    (net (code "99") (name "unconnected-(U4-Q0-Pad15)") (class "Default")
      (node (ref "U4") (pin "15") (pinfunction "Q0_15") (pintype "unspecified"))
    )
    (net (code "100") (name "unconnected-(U4-Q1-Pad1)") (class "Default")
      (node (ref "U4") (pin "1") (pinfunction "Q1_1") (pintype "unspecified"))
    )
    (net (code "101") (name "unconnected-(U4-Q2-Pad2)") (class "Default")
      (node (ref "U4") (pin "2") (pinfunction "Q2_2") (pintype "unspecified"))
    )
    (net (code "102") (name "unconnected-(U4-Q3-Pad3)") (class "Default")
      (node (ref "U4") (pin "3") (pinfunction "Q3_3") (pintype "unspecified"))
    )
    (net (code "103") (name "unconnected-(U5-1A-Pad1)") (class "Default")
      (node (ref "U5") (pin "1") (pinfunction "1A_1") (pintype "unspecified"))
    )
    (net (code "104") (name "unconnected-(U5-1B-Pad2)") (class "Default")
      (node (ref "U5") (pin "2") (pinfunction "1B_2") (pintype "unspecified"))
    )
    (net (code "105") (name "unconnected-(U5-1Y-Pad3)") (class "Default")
      (node (ref "U5") (pin "3") (pinfunction "1Y_3") (pintype "unspecified"))
    )
    (net (code "106") (name "unconnected-(U5-2A-Pad4)") (class "Default")
      (node (ref "U5") (pin "4") (pinfunction "2A_4") (pintype "unspecified"))
    )
    (net (code "107") (name "unconnected-(U5-2B-Pad5)") (class "Default")
      (node (ref "U5") (pin "5") (pinfunction "2B_5") (pintype "unspecified"))
    )
    (net (code "108") (name "unconnected-(U5-2Y-Pad6)") (class "Default")
      (node (ref "U5") (pin "6") (pinfunction "2Y_6") (pintype "unspecified"))
    )
    (net (code "109") (name "unconnected-(U6-A1-Pad2)") (class "Default")
      (node (ref "U6") (pin "2") (pinfunction "A1_2") (pintype "unspecified"))
    )
    (net (code "110") (name "unconnected-(U6-A2-Pad5)") (class "Default")
      (node (ref "U6") (pin "5") (pinfunction "A2_5") (pintype "unspecified"))
    )
    (net (code "111") (name "unconnected-(U6-B1-Pad3)") (class "Default")
      (node (ref "U6") (pin "3") (pinfunction "B1_3") (pintype "unspecified"))
    )
    (net (code "112") (name "unconnected-(U6-B2-Pad6)") (class "Default")
      (node (ref "U6") (pin "6") (pinfunction "B2_6") (pintype "unspecified"))
    )
    (net (code "113") (name "unconnected-(U6-Y1-Pad1)") (class "Default")
      (node (ref "U6") (pin "1") (pinfunction "Y1_1") (pintype "unspecified"))
    )
    (net (code "114") (name "unconnected-(U6-Y2-Pad4)") (class "Default")
      (node (ref "U6") (pin "4") (pinfunction "Y2_4") (pintype "unspecified"))
    )
    (net (code "115") (name "unconnected-(U11-Q1-Pad1)") (class "Default")
      (node (ref "U11") (pin "1") (pinfunction "Q1_1") (pintype "unspecified"))
    )
    (net (code "116") (name "unconnected-(U11-Q2-Pad2)") (class "Default")
      (node (ref "U11") (pin "2") (pinfunction "Q2_2") (pintype "unspecified"))
    )
    (net (code "117") (name "unconnected-(U11-Q3-Pad3)") (class "Default")
      (node (ref "U11") (pin "3") (pinfunction "Q3_3") (pintype "unspecified"))
    )
    (net (code "118") (name "unconnected-(U11-Q4-Pad4)") (class "Default")
      (node (ref "U11") (pin "4") (pinfunction "Q4_4") (pintype "unspecified"))
    )
    (net (code "119") (name "unconnected-(U11-Q5-Pad5)") (class "Default")
      (node (ref "U11") (pin "5") (pinfunction "Q5_5") (pintype "unspecified"))
    )
    (net (code "120") (name "unconnected-(U11-Q6-Pad6)") (class "Default")
      (node (ref "U11") (pin "6") (pinfunction "Q6_6") (pintype "unspecified"))
    )
    (net (code "121") (name "unconnected-(U11-Q7-Pad7)") (class "Default")
      (node (ref "U11") (pin "7") (pinfunction "Q7_7") (pintype "unspecified"))
    )
    (net (code "122") (name "unconnected-(U11-RCO#-Pad9)") (class "Default")
      (node (ref "U11") (pin "9") (pinfunction "RCO#_9") (pintype "unspecified"))
    )
  )
)
